# 01_Power_Control.net
KiCad netlist of a schematic drawn in Altium Designer
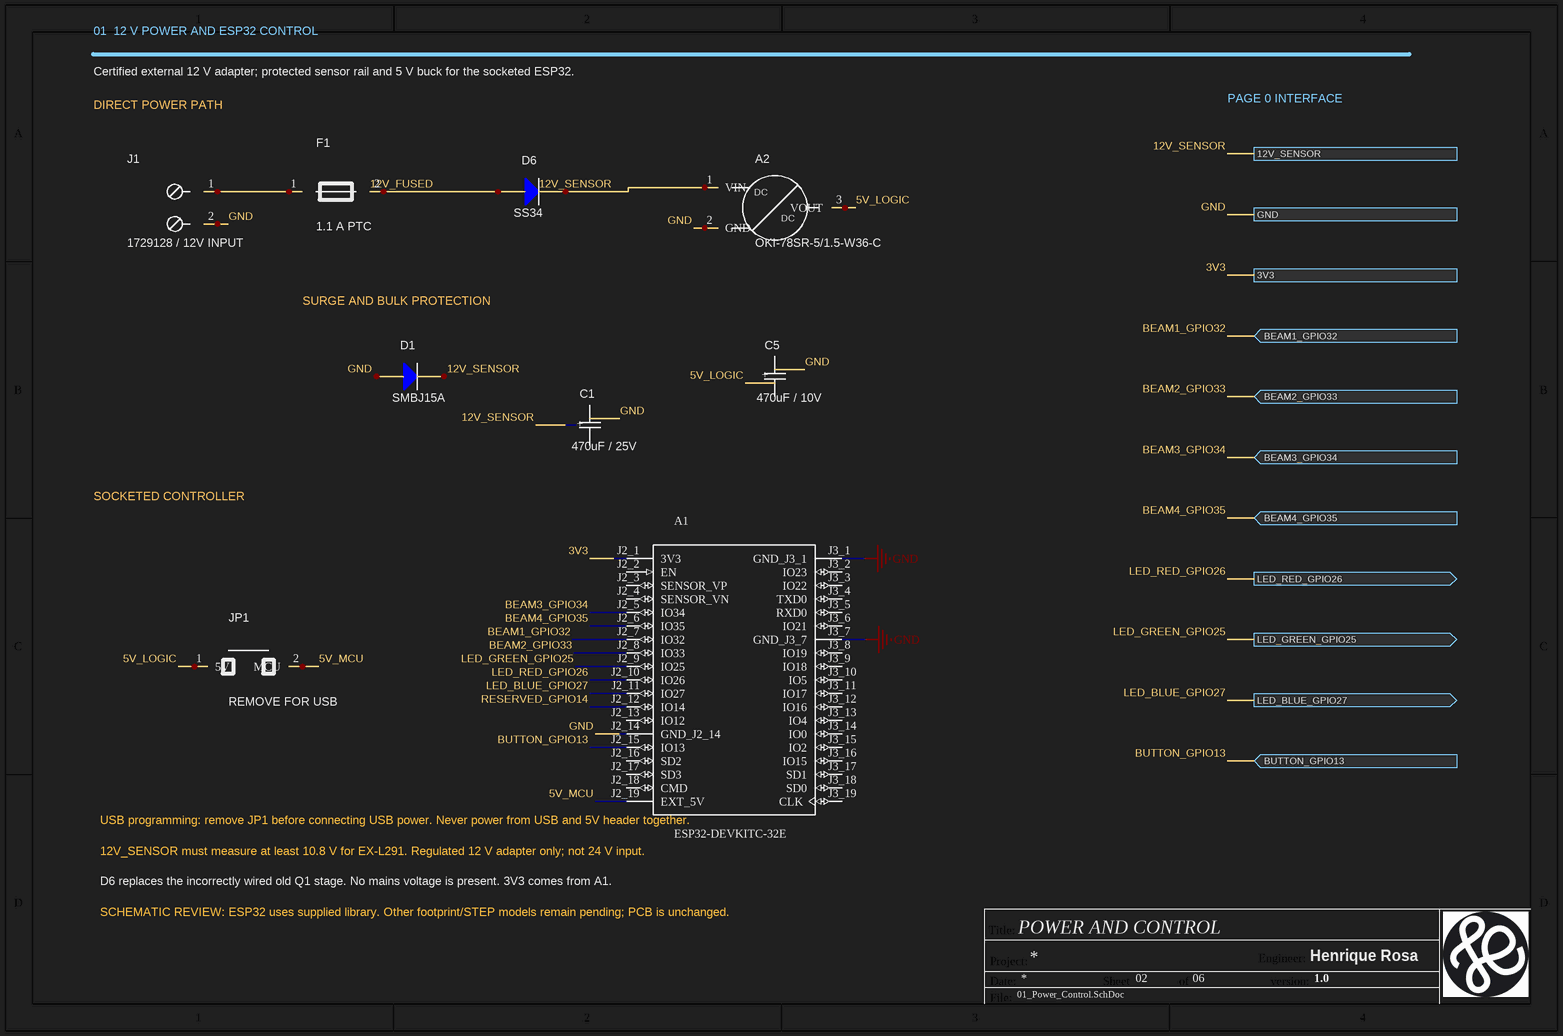
[diagram p0: 01_Power_Control.SchDoc]

(export (version "E")
  (design (tool "Eeschema 10.0.6"))
  (components
    (comp (ref "A1")
      (value "ESP32-DEVKITC-32E")
      (footprint "MODULE_ESP32-DEVKITC-32E")
      (fields
        (field (name "MF") "Espressif Systems")
        (field (name "MANUFACTURER PART NUMBER") "ESP32-DevKitC-32E")
      )
      (libsource (lib "*") (part "ESP32-DEVKITC-32E"))
    )
    (comp (ref "A2")
      (value "OKI-78SR-5/1.5-W36-C")
      (footprint "PartSpecificFootprints:MURATA_OKI78SR_VERTICAL")
      (description "12 V to regulated 5 V DC/DC module")
      (fields (field (name "MANUFACTURER") "Murata"))
      (libsource (lib "PartSpecificComponents") (part "MURATA_OKI_78SR_5_1P5"))
    )
    (comp (ref "C1")
      (value "470uF / 25V")
      (description "Protected 12 V bulk capacitor")
      (fields
        (field (name "MANUFACTURER") "Panasonic")
        (field (name "MANUFACTURER PART NUMBER") "EEU-FR1E471")
      )
      (libsource (lib "Miscellaneous Devices") (part "EEU-FR1E471"))
    )
    (comp (ref "C5")
      (value "470uF / 10V")
      (description "ESP32 Wi-Fi peak-current reservoir")
      (fields
        (field (name "MANUFACTURER") "Panasonic")
        (field (name "MANUFACTURER PART NUMBER") "EEU-FR1A471")
      )
      (libsource (lib "Miscellaneous Devices") (part "EEU-FR1A471"))
    )
    (comp (ref "D1")
      (value "SMBJ15A")
      (description "15 V TVS suppressor - cathode to positive rail")
      (fields (field (name "PART NUMBER") "FDLL4148") (field (name "MANUFACTURER") "Littelfuse"))
      (libsource (lib "Miscellaneous Devices") (part "SMBJ15A"))
    )
    (comp (ref "D6")
      (value "SS34")
      (description "Series reverse-polarity Schottky diode")
      (fields (field (name "PART NUMBER") "FDLL4148") (field (name "MANUFACTURER") "Vishay"))
      (libsource (lib "Miscellaneous Devices") (part "SS34-E3/57T"))
    )
    (comp (ref "F1")
      (value "1.1 A PTC")
      (description "Resettable 12 V input fuse")
      (fields (field (name "MANUFACTURER") "Bourns") (field (name "MANUFACTURER PART NUMBER") "MF-MSMF110-2"))
      (libsource (lib "*") (part "MF-MSMF110-2"))
    )
    (comp (ref "J1")
      (value "1729128 / 12V INPUT")
      (footprint "PartSpecificFootprints:PHOENIX_1729128_MKDSN_2_508")
      (description "Two-position 5.08 mm screw terminal")
      (fields
        (field (name "MANUFACTURER") "Phoenix Contact")
        (field (name "MANUFACTURER PART NUMBER") "1729128")
      )
      (libsource (lib "PartSpecificComponents") (part "PHOENIX_1729128"))
    )
    (comp (ref "JP1")
      (value "REMOVE FOR USB")
      (description "External 5 V disconnect; fit shunt only without USB")
      (fields
        (field (name "MANUFACTURER") "Samtec")
        (field (name "MANUFACTURER PART NUMBER") "TSW-102-07-G-S")
      )
      (libsource (lib "*") (part "TSW-102-07-G-S"))
    )
  )
  (nets
    (net (code "1") (name "/3V3") (class "Default")
      (node (ref "A1") (pin "J2_1") (pinfunction "3V3_J2_1") (pintype "power_in"))
    )
    (net (code "2") (name "/5V_LOGIC") (class "Default")
      (node (ref "A2") (pin "3") (pinfunction "VOUT_3") (pintype "passive"))
      (node (ref "JP1") (pin "1") (pinfunction "5V_1") (pintype "passive"))
    )
    (net (code "3") (name "/5V_MCU") (class "Default")
      (node (ref "A1") (pin "J2_19") (pinfunction "EXT_5V_J2_19") (pintype "power_in"))
      (node (ref "JP1") (pin "2") (pinfunction "MCU_2") (pintype "passive"))
    )
    (net (code "4") (name "/12V_FUSED") (class "Default")
      (node (ref "D6") (pin "1") (pinfunction "A_1") (pintype "passive"))
      (node (ref "F1") (pin "2") (pintype "passive"))
    )
    (net (code "5") (name "/12V_SENSOR") (class "Default")
      (node (ref "A2") (pin "1") (pinfunction "VIN_1") (pintype "passive"))
      (node (ref "D1") (pin "2") (pinfunction "K_2") (pintype "passive"))
      (node (ref "D6") (pin "2") (pinfunction "K_2") (pintype "passive"))
    )
    (net (code "6") (name "/BEAM1_GPIO32") (class "Default")
      (node (ref "A1") (pin "J2_7") (pinfunction "IO32_J2_7") (pintype "bidirectional"))
    )
    (net (code "7") (name "/BEAM2_GPIO33") (class "Default")
      (node (ref "A1") (pin "J2_8") (pinfunction "IO33_J2_8") (pintype "bidirectional"))
    )
    (net (code "8") (name "/BEAM3_GPIO34") (class "Default")
      (node (ref "A1") (pin "J2_5") (pinfunction "IO34_J2_5") (pintype "bidirectional"))
    )
    (net (code "9") (name "/BEAM4_GPIO35") (class "Default")
      (node (ref "A1") (pin "J2_6") (pinfunction "IO35_J2_6") (pintype "bidirectional"))
    )
    (net (code "10") (name "/BUTTON_GPIO13") (class "Default")
      (node (ref "A1") (pin "J2_15") (pinfunction "IO13_J2_15") (pintype "bidirectional"))
    )
    (net (code "11") (name "/LED_BLUE_GPIO27") (class "Default")
      (node (ref "A1") (pin "J2_11") (pinfunction "IO27_J2_11") (pintype "bidirectional"))
    )
    (net (code "12") (name "/LED_GREEN_GPIO25") (class "Default")
      (node (ref "A1") (pin "J2_9") (pinfunction "IO25_J2_9") (pintype "bidirectional"))
    )
    (net (code "13") (name "/LED_RED_GPIO26") (class "Default")
      (node (ref "A1") (pin "J2_10") (pinfunction "IO26_J2_10") (pintype "bidirectional"))
    )
    (net (code "14") (name "/RESERVED_GPIO14") (class "Default")
      (node (ref "A1") (pin "J2_12") (pinfunction "IO14_J2_12") (pintype "bidirectional"))
    )
    (net (code "15") (name "GND") (class "Default")
      (node (ref "A1") (pin "J2_14") (pinfunction "GND_J2_14_J2_14") (pintype "power_in"))
      (node (ref "A1") (pin "J3_1") (pinfunction "GND_J3_1_J3_1") (pintype "power_in"))
      (node (ref "A1") (pin "J3_7") (pinfunction "GND_J3_7_J3_7") (pintype "power_in"))
      (node (ref "A2") (pin "2") (pinfunction "GND_2") (pintype "passive"))
      (node (ref "D1") (pin "1") (pinfunction "A_1") (pintype "passive"))
      (node (ref "J1") (pin "2") (pinfunction "0V_2") (pintype "power_in"))
    )
    (net (code "16") (name "Net-(J1-+12V)") (class "Default")
      (node (ref "F1") (pin "1") (pintype "passive"))
      (node (ref "J1") (pin "1") (pinfunction "+12V_1") (pintype "power_in"))
    )
    (net (code "17") (name "unconnected-(A1-CLK-PadJ3_19)") (class "Default")
      (node (ref "A1") (pin "J3_19") (pinfunction "CLK_J3_19") (pintype "bidirectional"))
    )
    (net (code "18") (name "unconnected-(A1-CMD-PadJ2_18)") (class "Default")
      (node (ref "A1") (pin "J2_18") (pinfunction "CMD_J2_18") (pintype "bidirectional"))
    )
    (net (code "19") (name "unconnected-(A1-EN-PadJ2_2)") (class "Default")
      (node (ref "A1") (pin "J2_2") (pinfunction "EN_J2_2") (pintype "input"))
    )
    (net (code "20") (name "unconnected-(A1-IO0-PadJ3_14)") (class "Default")
      (node (ref "A1") (pin "J3_14") (pinfunction "IO0_J3_14") (pintype "bidirectional"))
    )
    (net (code "21") (name "unconnected-(A1-IO2-PadJ3_15)") (class "Default")
      (node (ref "A1") (pin "J3_15") (pinfunction "IO2_J3_15") (pintype "bidirectional"))
    )
    (net (code "22") (name "unconnected-(A1-IO4-PadJ3_13)") (class "Default")
      (node (ref "A1") (pin "J3_13") (pinfunction "IO4_J3_13") (pintype "bidirectional"))
    )
    (net (code "23") (name "unconnected-(A1-IO5-PadJ3_10)") (class "Default")
      (node (ref "A1") (pin "J3_10") (pinfunction "IO5_J3_10") (pintype "bidirectional"))
    )
    (net (code "24") (name "unconnected-(A1-IO12-PadJ2_13)") (class "Default")
      (node (ref "A1") (pin "J2_13") (pinfunction "IO12_J2_13") (pintype "bidirectional"))
    )
    (net (code "25") (name "unconnected-(A1-IO15-PadJ3_16)") (class "Default")
      (node (ref "A1") (pin "J3_16") (pinfunction "IO15_J3_16") (pintype "bidirectional"))
    )
    (net (code "26") (name "unconnected-(A1-IO16-PadJ3_12)") (class "Default")
      (node (ref "A1") (pin "J3_12") (pinfunction "IO16_J3_12") (pintype "bidirectional"))
    )
    (net (code "27") (name "unconnected-(A1-IO17-PadJ3_11)") (class "Default")
      (node (ref "A1") (pin "J3_11") (pinfunction "IO17_J3_11") (pintype "bidirectional"))
    )
    (net (code "28") (name "unconnected-(A1-IO18-PadJ3_9)") (class "Default")
      (node (ref "A1") (pin "J3_9") (pinfunction "IO18_J3_9") (pintype "bidirectional"))
    )
    (net (code "29") (name "unconnected-(A1-IO19-PadJ3_8)") (class "Default")
      (node (ref "A1") (pin "J3_8") (pinfunction "IO19_J3_8") (pintype "bidirectional"))
    )
    (net (code "30") (name "unconnected-(A1-IO21-PadJ3_6)") (class "Default")
      (node (ref "A1") (pin "J3_6") (pinfunction "IO21_J3_6") (pintype "bidirectional"))
    )
    (net (code "31") (name "unconnected-(A1-IO22-PadJ3_3)") (class "Default")
      (node (ref "A1") (pin "J3_3") (pinfunction "IO22_J3_3") (pintype "bidirectional"))
    )
    (net (code "32") (name "unconnected-(A1-IO23-PadJ3_2)") (class "Default")
      (node (ref "A1") (pin "J3_2") (pinfunction "IO23_J3_2") (pintype "bidirectional"))
    )
    (net (code "33") (name "unconnected-(A1-RXD0-PadJ3_5)") (class "Default")
      (node (ref "A1") (pin "J3_5") (pinfunction "RXD0_J3_5") (pintype "bidirectional"))
    )
    (net (code "34") (name "unconnected-(A1-SD0-PadJ3_18)") (class "Default")
      (node (ref "A1") (pin "J3_18") (pinfunction "SD0_J3_18") (pintype "bidirectional"))
    )
    (net (code "35") (name "unconnected-(A1-SD1-PadJ3_17)") (class "Default")
      (node (ref "A1") (pin "J3_17") (pinfunction "SD1_J3_17") (pintype "bidirectional"))
    )
    (net (code "36") (name "unconnected-(A1-SD2-PadJ2_16)") (class "Default")
      (node (ref "A1") (pin "J2_16") (pinfunction "SD2_J2_16") (pintype "bidirectional"))
    )
    (net (code "37") (name "unconnected-(A1-SD3-PadJ2_17)") (class "Default")
      (node (ref "A1") (pin "J2_17") (pinfunction "SD3_J2_17") (pintype "bidirectional"))
    )
    (net (code "38") (name "unconnected-(A1-SENSOR_VN-PadJ2_4)") (class "Default")
      (node (ref "A1") (pin "J2_4") (pinfunction "SENSOR_VN_J2_4") (pintype "bidirectional"))
    )
    (net (code "39") (name "unconnected-(A1-SENSOR_VP-PadJ2_3)") (class "Default")
      (node (ref "A1") (pin "J2_3") (pinfunction "SENSOR_VP_J2_3") (pintype "bidirectional"))
    )
    (net (code "40") (name "unconnected-(A1-TXD0-PadJ3_4)") (class "Default")
      (node (ref "A1") (pin "J3_4") (pinfunction "TXD0_J3_4") (pintype "bidirectional"))
    )
    (net (code "41") (name "unconnected-(C1-Pad1)") (class "Default")
      (node (ref "C1") (pin "1") (pinfunction "1_1") (pintype "passive"))
    )
    (net (code "42") (name "unconnected-(C1-Pad2)") (class "Default")
      (node (ref "C1") (pin "2") (pinfunction "2_2") (pintype "passive"))
    )
    (net (code "43") (name "unconnected-(C5-Pad1)") (class "Default")
      (node (ref "C5") (pin "1") (pinfunction "1_1") (pintype "passive"))
    )
    (net (code "44") (name "unconnected-(C5-Pad2)") (class "Default")
      (node (ref "C5") (pin "2") (pinfunction "2_2") (pintype "passive"))
    )
  )
)
